# LB-word-charsBuffer.net
KiCad netlist of a schematic drawn in Altium Designer
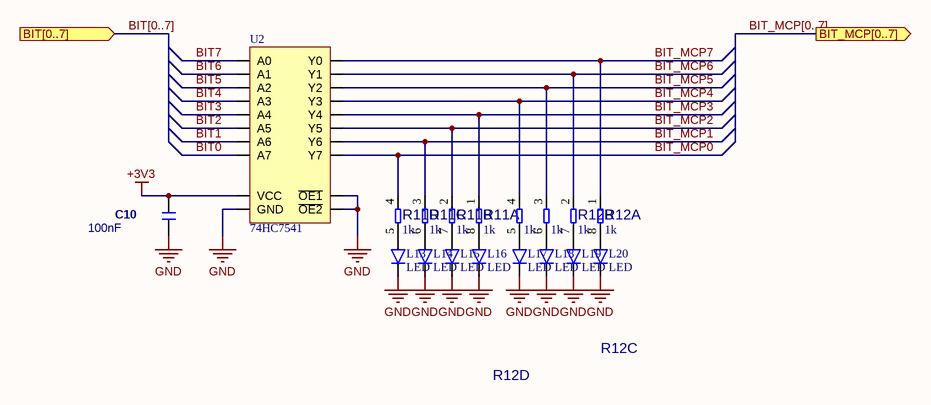
[diagram p0: LB-word-charsBuffer.SchDoc]

(export (version "E")
  (design (tool "Eeschema 10.0.6"))
  (components
    (comp (ref "C10")
      (value "100nF")
      (footprint "C0603_N")
      (description "Capacitor MLCC")
      (fields
        (field (name "MANUFACTURER") "Yageo")
        (field (name "MANUFACTURER PART NUMBER") "CC0603KRX7R9BB104")
      )
      (libsource (lib "wes") (part "Capacitor"))
    )
    (comp (ref "L13") (value "LED") (footprint "LED 0603/1608") (libsource (lib "wes") (part "LED")))
    (comp (ref "L14") (value "LED") (footprint "LED 0603/1608") (libsource (lib "wes") (part "LED")))
    (comp (ref "L15") (value "LED") (footprint "LED 0603/1608") (libsource (lib "wes") (part "LED")))
    (comp (ref "L16") (value "LED") (footprint "LED 0603/1608") (libsource (lib "wes") (part "LED")))
    (comp (ref "L17") (value "LED") (footprint "LED 0603/1608") (libsource (lib "wes") (part "LED")))
    (comp (ref "L18") (value "LED") (footprint "LED 0603/1608") (libsource (lib "wes") (part "LED")))
    (comp (ref "L19") (value "LED") (footprint "LED 0603/1608") (libsource (lib "wes") (part "LED")))
    (comp (ref "L20") (value "LED") (footprint "LED 0603/1608") (libsource (lib "wes") (part "LED")))
    (comp (ref "R11")
      (value "1k")
      (footprint "YC164")
      (fields (field (name "Comment") "; 1k"))
      (libsource (lib "wes") (part "Resistor Array - 4P"))
    )
    (comp (ref "R12")
      (value "1k")
      (footprint "YC164")
      (fields (field (name "Comment") "; 1k"))
      (libsource (lib "wes") (part "Resistor Array - 4P"))
    )
    (comp (ref "U2")
      (value "74HC7541")
      (footprint "TSSOP20_N")
      (description "Schmitt Trigger Octal")
      (libsource (lib "wes") (part "74HC7541"))
    )
  )
  (nets
    (net (code "1") (name "+3V3") (class "Default")
      (node (ref "C10") (pin "1") (pintype "passive"))
      (node (ref "U2") (pin "20") (pinfunction "VCC_20") (pintype "passive"))
    )
    (net (code "2") (name "/BIT0") (class "Default")
      (node (ref "U2") (pin "9") (pinfunction "A7_9") (pintype "passive"))
    )
    (net (code "3") (name "/BIT1") (class "Default")
      (node (ref "U2") (pin "8") (pinfunction "A6_8") (pintype "passive"))
    )
    (net (code "4") (name "/BIT2") (class "Default")
      (node (ref "U2") (pin "7") (pinfunction "A5_7") (pintype "passive"))
    )
    (net (code "5") (name "/BIT3") (class "Default")
      (node (ref "U2") (pin "6") (pinfunction "A4_6") (pintype "passive"))
    )
    (net (code "6") (name "/BIT4") (class "Default")
      (node (ref "U2") (pin "5") (pinfunction "A3_5") (pintype "passive"))
    )
    (net (code "7") (name "/BIT5") (class "Default")
      (node (ref "U2") (pin "4") (pinfunction "A2_4") (pintype "passive"))
    )
    (net (code "8") (name "/BIT6") (class "Default")
      (node (ref "U2") (pin "3") (pinfunction "A1_3") (pintype "passive"))
    )
    (net (code "9") (name "/BIT7") (class "Default")
      (node (ref "U2") (pin "2") (pinfunction "A0_2") (pintype "passive"))
    )
    (net (code "11") (name "/BIT_MCP0") (class "Default")
      (node (ref "R11") (pin "4") (pinfunction "4_4") (pintype "passive"))
      (node (ref "U2") (pin "11") (pinfunction "Y7_11") (pintype "passive"))
    )
    (net (code "12") (name "/BIT_MCP1") (class "Default")
      (node (ref "R11") (pin "3") (pinfunction "3_3") (pintype "passive"))
      (node (ref "U2") (pin "12") (pinfunction "Y6_12") (pintype "passive"))
    )
    (net (code "13") (name "/BIT_MCP2") (class "Default")
      (node (ref "R11") (pin "2") (pinfunction "2_2") (pintype "passive"))
      (node (ref "U2") (pin "13") (pinfunction "Y5_13") (pintype "passive"))
    )
    (net (code "14") (name "/BIT_MCP3") (class "Default")
      (node (ref "R11") (pin "1") (pinfunction "1_1") (pintype "passive"))
      (node (ref "U2") (pin "14") (pinfunction "Y4_14") (pintype "passive"))
    )
    (net (code "15") (name "/BIT_MCP4") (class "Default")
      (node (ref "R12") (pin "4") (pinfunction "4_4") (pintype "passive"))
      (node (ref "U2") (pin "15") (pinfunction "Y3_15") (pintype "passive"))
    )
    (net (code "16") (name "/BIT_MCP5") (class "Default")
      (node (ref "R12") (pin "3") (pinfunction "3_3") (pintype "passive"))
      (node (ref "U2") (pin "16") (pinfunction "Y2_16") (pintype "passive"))
    )
    (net (code "17") (name "/BIT_MCP6") (class "Default")
      (node (ref "R12") (pin "2") (pinfunction "2_2") (pintype "passive"))
      (node (ref "U2") (pin "17") (pinfunction "Y1_17") (pintype "passive"))
    )
    (net (code "18") (name "/BIT_MCP7") (class "Default")
      (node (ref "R12") (pin "1") (pinfunction "1_1") (pintype "passive"))
      (node (ref "U2") (pin "18") (pinfunction "Y0_18") (pintype "passive"))
    )
    (net (code "20") (name "GND") (class "Default")
      (node (ref "C10") (pin "2") (pintype "passive"))
      (node (ref "L13") (pin "1") (pinfunction "K_1") (pintype "power_in"))
      (node (ref "L14") (pin "1") (pinfunction "K_1") (pintype "power_in"))
      (node (ref "L15") (pin "1") (pinfunction "K_1") (pintype "power_in"))
      (node (ref "L16") (pin "1") (pinfunction "K_1") (pintype "power_in"))
      (node (ref "L17") (pin "1") (pinfunction "K_1") (pintype "power_in"))
      (node (ref "L18") (pin "1") (pinfunction "K_1") (pintype "power_in"))
      (node (ref "L19") (pin "1") (pinfunction "K_1") (pintype "power_in"))
      (node (ref "L20") (pin "1") (pinfunction "K_1") (pintype "power_in"))
      (node (ref "U2") (pin "1") (pinfunction "~{OE1}_1") (pintype "passive"))
      (node (ref "U2") (pin "10") (pinfunction "GND_10") (pintype "passive"))
      (node (ref "U2") (pin "19") (pinfunction "~{OE2}_19") (pintype "passive"))
    )
    (net (code "21") (name "Net-(L13-A)") (class "Default")
      (node (ref "L13") (pin "2") (pinfunction "A_2") (pintype "power_in"))
      (node (ref "R11") (pin "5") (pinfunction "5_5") (pintype "passive"))
    )
    (net (code "22") (name "Net-(L14-A)") (class "Default")
      (node (ref "L14") (pin "2") (pinfunction "A_2") (pintype "power_in"))
      (node (ref "R11") (pin "6") (pinfunction "6_6") (pintype "passive"))
    )
    (net (code "23") (name "Net-(L15-A)") (class "Default")
      (node (ref "L15") (pin "2") (pinfunction "A_2") (pintype "power_in"))
      (node (ref "R11") (pin "7") (pinfunction "7_7") (pintype "passive"))
    )
    (net (code "24") (name "Net-(L16-A)") (class "Default")
      (node (ref "L16") (pin "2") (pinfunction "A_2") (pintype "power_in"))
      (node (ref "R11") (pin "8") (pinfunction "8_8") (pintype "passive"))
    )
    (net (code "25") (name "Net-(L17-A)") (class "Default")
      (node (ref "L17") (pin "2") (pinfunction "A_2") (pintype "power_in"))
      (node (ref "R12") (pin "5") (pinfunction "5_5") (pintype "passive"))
    )
    (net (code "26") (name "Net-(L18-A)") (class "Default")
      (node (ref "L18") (pin "2") (pinfunction "A_2") (pintype "power_in"))
      (node (ref "R12") (pin "6") (pinfunction "6_6") (pintype "passive"))
    )
    (net (code "27") (name "Net-(L19-A)") (class "Default")
      (node (ref "L19") (pin "2") (pinfunction "A_2") (pintype "power_in"))
      (node (ref "R12") (pin "7") (pinfunction "7_7") (pintype "passive"))
    )
    (net (code "28") (name "Net-(L20-A)") (class "Default")
      (node (ref "L20") (pin "2") (pinfunction "A_2") (pintype "power_in"))
      (node (ref "R12") (pin "8") (pinfunction "8_8") (pintype "passive"))
    )
  )
)
